# AlphaNumeric_Featherwing_rev_A.net
KiCad netlist of a schematic drawn in EAGLE
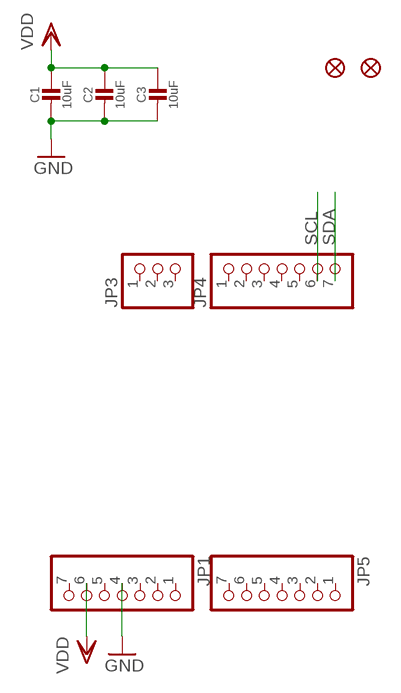
[diagram p0: schematic, sheet 1, part 1 of 2]
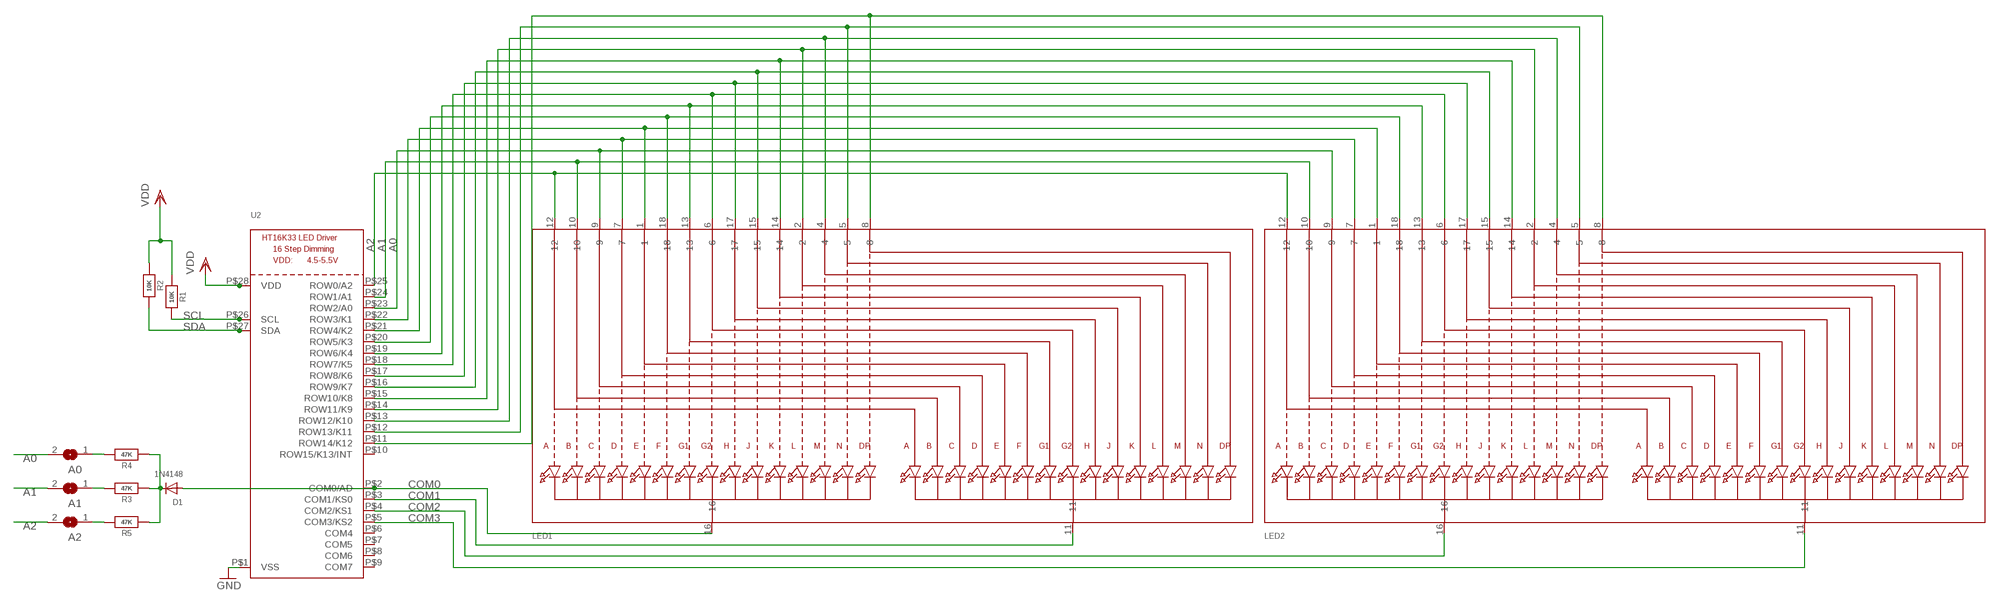
[diagram p1: schematic, sheet 1, part 2 of 2]

(export (version "E")
  (design (tool "Eeschema 10.0.6"))
  (components
    (comp (ref "A0")
      (value "SOLDERJUMPERREFLOW_NOPASTE")
      (footprint "eagle-import:SOLDERJUMPER_REFLOW_NOPASTE")
      (libsource (lib "eagle-import") (part "SOLDERJUMPERREFLOW_NOPASTE"))
    )
    (comp (ref "A1")
      (value "SOLDERJUMPERREFLOW_NOPASTE")
      (footprint "eagle-import:SOLDERJUMPER_REFLOW_NOPASTE")
      (libsource (lib "eagle-import") (part "SOLDERJUMPERREFLOW_NOPASTE"))
    )
    (comp (ref "A2")
      (value "SOLDERJUMPERREFLOW_NOPASTE")
      (footprint "eagle-import:SOLDERJUMPER_REFLOW_NOPASTE")
      (libsource (lib "eagle-import") (part "SOLDERJUMPERREFLOW_NOPASTE"))
    )
    (comp (ref "C1")
      (value "10uF")
      (footprint "eagle-import:0805-NO")
      (libsource (lib "eagle-import") (part "CAP_CERAMIC0805-NOOUTLINE"))
    )
    (comp (ref "C2")
      (value "10uF")
      (footprint "eagle-import:0805-NO")
      (libsource (lib "eagle-import") (part "CAP_CERAMIC0805-NOOUTLINE"))
    )
    (comp (ref "C3")
      (value "10uF")
      (footprint "eagle-import:0805-NO")
      (libsource (lib "eagle-import") (part "CAP_CERAMIC0805-NOOUTLINE"))
    )
    (comp (ref "D1")
      (value "1N4148")
      (footprint "eagle-import:SOD-323F")
      (libsource (lib "eagle-import") (part "DIODESOD-323F"))
    )
    (comp (ref "JP1")
      (value "HEADER-1X770MIL")
      (footprint "eagle-import:1X07_ROUND_70")
      (libsource (lib "eagle-import") (part "HEADER-1X770MIL"))
    )
    (comp (ref "JP3")
      (value "HEADER-1X3ROUND")
      (footprint "eagle-import:1X03_ROUND")
      (libsource (lib "eagle-import") (part "HEADER-1X3ROUND"))
    )
    (comp (ref "JP4")
      (value "HEADER-1X770MIL")
      (footprint "eagle-import:1X07_ROUND_70")
      (libsource (lib "eagle-import") (part "HEADER-1X770MIL"))
    )
    (comp (ref "JP5")
      (value "HEADER-1X770MIL")
      (footprint "eagle-import:1X07_ROUND_70")
      (libsource (lib "eagle-import") (part "HEADER-1X770MIL"))
    )
    (comp (ref "LED1")
      (value "DISP_SEGMENT_STARBURST_DUAL_COMMONCATHODE")
      (footprint "eagle-import:SEGMENT_STARTBUST_DUAL_KWA-541CBB")
      (libsource (lib "eagle-import") (part "DISP_SEGMENT_STARBURST_DUAL_COMMONCATHODE"))
    )
    (comp (ref "LED2")
      (value "DISP_SEGMENT_STARBURST_DUAL_COMMONCATHODE")
      (footprint "eagle-import:SEGMENT_STARTBUST_DUAL_KWA-541CBB")
      (libsource (lib "eagle-import") (part "DISP_SEGMENT_STARBURST_DUAL_COMMONCATHODE"))
    )
    (comp (ref "R1")
      (value "10K")
      (footprint "eagle-import:0805-NO")
      (libsource (lib "eagle-import") (part "RESISTOR0805_NOOUTLINE"))
    )
    (comp (ref "R2")
      (value "10K")
      (footprint "eagle-import:0805-NO")
      (libsource (lib "eagle-import") (part "RESISTOR0805_NOOUTLINE"))
    )
    (comp (ref "R3")
      (value "47K")
      (footprint "eagle-import:0805-NO")
      (libsource (lib "eagle-import") (part "RESISTOR0805_NOOUTLINE"))
    )
    (comp (ref "R4")
      (value "47K")
      (footprint "eagle-import:0805-NO")
      (libsource (lib "eagle-import") (part "RESISTOR0805_NOOUTLINE"))
    )
    (comp (ref "R5")
      (value "47K")
      (footprint "eagle-import:0805-NO")
      (libsource (lib "eagle-import") (part "RESISTOR0805_NOOUTLINE"))
    )
    (comp (ref "U$1")
      (value "FIDUCIAL\"\"")
      (footprint "eagle-import:FIDUCIAL_1MM")
      (libsource (lib "eagle-import") (part "FIDUCIAL{dblquote}{dblquote}"))
    )
    (comp (ref "U$2")
      (value "FIDUCIAL\"\"")
      (footprint "eagle-import:FIDUCIAL_1MM")
      (libsource (lib "eagle-import") (part "FIDUCIAL{dblquote}{dblquote}"))
    )
    (comp (ref "U2")
      (value "HT16K33_SOP28_SKINNY")
      (footprint "eagle-import:SOP28_300MIL_SKINNY")
      (libsource (lib "eagle-import") (part "HT16K33_SOP28_SKINNY"))
    )
  )
  (nets
    (net (code "1") (name "/A0") (class "Default")
      (node (ref "A0") (pin "2") (pinfunction "2_2") (pintype "passive"))
      (node (ref "LED1") (pin "9") (pinfunction "9_9") (pintype "bidirectional"))
      (node (ref "LED2") (pin "9") (pinfunction "9_9") (pintype "bidirectional"))
      (node (ref "U2") (pin "P$23") (pinfunction "ROW2/A0_P$23") (pintype "bidirectional"))
    )
    (net (code "2") (name "/A1") (class "Default")
      (node (ref "A1") (pin "2") (pinfunction "2_2") (pintype "passive"))
      (node (ref "LED1") (pin "10") (pinfunction "10_10") (pintype "bidirectional"))
      (node (ref "LED2") (pin "10") (pinfunction "10_10") (pintype "bidirectional"))
      (node (ref "U2") (pin "P$24") (pinfunction "ROW1/A1_P$24") (pintype "bidirectional"))
    )
    (net (code "3") (name "/A2") (class "Default")
      (node (ref "A2") (pin "2") (pinfunction "2_2") (pintype "passive"))
      (node (ref "LED1") (pin "12") (pinfunction "12_12") (pintype "bidirectional"))
      (node (ref "LED2") (pin "12") (pinfunction "12_12") (pintype "bidirectional"))
      (node (ref "U2") (pin "P$25") (pinfunction "ROW0/A2_P$25") (pintype "bidirectional"))
    )
    (net (code "4") (name "/COM0") (class "Default")
      (node (ref "D1") (pin "A") (pinfunction "A_A") (pintype "passive"))
      (node (ref "LED1") (pin "16") (pinfunction "16_16") (pintype "bidirectional"))
      (node (ref "U2") (pin "P$2") (pinfunction "COM0/AD_P$2") (pintype "bidirectional"))
    )
    (net (code "5") (name "/COM1") (class "Default")
      (node (ref "LED1") (pin "11") (pinfunction "11_11") (pintype "bidirectional"))
      (node (ref "U2") (pin "P$3") (pinfunction "COM1/KS0_P$3") (pintype "bidirectional"))
    )
    (net (code "6") (name "/COM2") (class "Default")
      (node (ref "LED2") (pin "16") (pinfunction "16_16") (pintype "bidirectional"))
      (node (ref "U2") (pin "P$4") (pinfunction "COM2/KS1_P$4") (pintype "bidirectional"))
    )
    (net (code "7") (name "/COM3") (class "Default")
      (node (ref "LED2") (pin "11") (pinfunction "11_11") (pintype "bidirectional"))
      (node (ref "U2") (pin "P$5") (pinfunction "COM3/KS2_P$5") (pintype "bidirectional"))
    )
    (net (code "8") (name "/SCL") (class "Default")
      (node (ref "JP4") (pin "6") (pinfunction "6_6") (pintype "passive"))
      (node (ref "R1") (pin "2") (pinfunction "2_2") (pintype "passive"))
      (node (ref "U2") (pin "P$26") (pinfunction "SCL_P$26") (pintype "bidirectional"))
    )
    (net (code "9") (name "/SDA") (class "Default")
      (node (ref "JP4") (pin "7") (pinfunction "7_7") (pintype "passive"))
      (node (ref "R2") (pin "2") (pinfunction "2_2") (pintype "passive"))
      (node (ref "U2") (pin "P$27") (pinfunction "SDA_P$27") (pintype "bidirectional"))
    )
    (net (code "10") (name "GND") (class "Default")
      (node (ref "C1") (pin "2") (pinfunction "2_2") (pintype "passive"))
      (node (ref "C2") (pin "2") (pinfunction "2_2") (pintype "passive"))
      (node (ref "C3") (pin "2") (pinfunction "2_2") (pintype "passive"))
      (node (ref "JP1") (pin "4") (pinfunction "4_4") (pintype "passive"))
      (node (ref "U2") (pin "P$1") (pinfunction "VSS_P$1") (pintype "bidirectional"))
    )
    (net (code "11") (name "Net-(A0-Pad1)") (class "Default")
      (node (ref "A0") (pin "1") (pinfunction "1_1") (pintype "passive"))
      (node (ref "R4") (pin "2") (pinfunction "2_2") (pintype "passive"))
    )
    (net (code "12") (name "Net-(A1-Pad1)") (class "Default")
      (node (ref "A1") (pin "1") (pinfunction "1_1") (pintype "passive"))
      (node (ref "R3") (pin "2") (pinfunction "2_2") (pintype "passive"))
    )
    (net (code "13") (name "Net-(A2-Pad1)") (class "Default")
      (node (ref "A2") (pin "1") (pinfunction "1_1") (pintype "passive"))
      (node (ref "R5") (pin "2") (pinfunction "2_2") (pintype "passive"))
    )
    (net (code "14") (name "Net-(D1-PadC)") (class "Default")
      (node (ref "D1") (pin "C") (pinfunction "C_C") (pintype "passive"))
      (node (ref "R3") (pin "1") (pinfunction "1_1") (pintype "passive"))
      (node (ref "R4") (pin "1") (pinfunction "1_1") (pintype "passive"))
      (node (ref "R5") (pin "1") (pinfunction "1_1") (pintype "passive"))
    )
    (net (code "15") (name "Net-(U2-ROW3{slash}K1)") (class "Default")
      (node (ref "LED1") (pin "7") (pinfunction "7_7") (pintype "bidirectional"))
      (node (ref "LED2") (pin "7") (pinfunction "7_7") (pintype "bidirectional"))
      (node (ref "U2") (pin "P$22") (pinfunction "ROW3/K1_P$22") (pintype "bidirectional"))
    )
    (net (code "16") (name "Net-(U2-ROW4{slash}K2)") (class "Default")
      (node (ref "LED1") (pin "1") (pinfunction "1_1") (pintype "bidirectional"))
      (node (ref "LED2") (pin "1") (pinfunction "1_1") (pintype "bidirectional"))
      (node (ref "U2") (pin "P$21") (pinfunction "ROW4/K2_P$21") (pintype "bidirectional"))
    )
    (net (code "17") (name "Net-(U2-ROW5{slash}K3)") (class "Default")
      (node (ref "LED1") (pin "18") (pinfunction "18_18") (pintype "bidirectional"))
      (node (ref "LED2") (pin "18") (pinfunction "18_18") (pintype "bidirectional"))
      (node (ref "U2") (pin "P$20") (pinfunction "ROW5/K3_P$20") (pintype "bidirectional"))
    )
    (net (code "18") (name "Net-(U2-ROW6{slash}K4)") (class "Default")
      (node (ref "LED1") (pin "13") (pinfunction "13_13") (pintype "bidirectional"))
      (node (ref "LED2") (pin "13") (pinfunction "13_13") (pintype "bidirectional"))
      (node (ref "U2") (pin "P$19") (pinfunction "ROW6/K4_P$19") (pintype "bidirectional"))
    )
    (net (code "19") (name "Net-(U2-ROW7{slash}K5)") (class "Default")
      (node (ref "LED1") (pin "6") (pinfunction "6_6") (pintype "bidirectional"))
      (node (ref "LED2") (pin "6") (pinfunction "6_6") (pintype "bidirectional"))
      (node (ref "U2") (pin "P$18") (pinfunction "ROW7/K5_P$18") (pintype "bidirectional"))
    )
    (net (code "20") (name "Net-(U2-ROW8{slash}K6)") (class "Default")
      (node (ref "LED1") (pin "17") (pinfunction "17_17") (pintype "bidirectional"))
      (node (ref "LED2") (pin "17") (pinfunction "17_17") (pintype "bidirectional"))
      (node (ref "U2") (pin "P$17") (pinfunction "ROW8/K6_P$17") (pintype "bidirectional"))
    )
    (net (code "21") (name "Net-(U2-ROW9{slash}K7)") (class "Default")
      (node (ref "LED1") (pin "15") (pinfunction "15_15") (pintype "bidirectional"))
      (node (ref "LED2") (pin "15") (pinfunction "15_15") (pintype "bidirectional"))
      (node (ref "U2") (pin "P$16") (pinfunction "ROW9/K7_P$16") (pintype "bidirectional"))
    )
    (net (code "22") (name "Net-(U2-ROW10{slash}K8)") (class "Default")
      (node (ref "LED1") (pin "14") (pinfunction "14_14") (pintype "bidirectional"))
      (node (ref "LED2") (pin "14") (pinfunction "14_14") (pintype "bidirectional"))
      (node (ref "U2") (pin "P$15") (pinfunction "ROW10/K8_P$15") (pintype "bidirectional"))
    )
    (net (code "23") (name "Net-(U2-ROW11{slash}K9)") (class "Default")
      (node (ref "LED1") (pin "2") (pinfunction "2_2") (pintype "bidirectional"))
      (node (ref "LED2") (pin "2") (pinfunction "2_2") (pintype "bidirectional"))
      (node (ref "U2") (pin "P$14") (pinfunction "ROW11/K9_P$14") (pintype "bidirectional"))
    )
    (net (code "24") (name "Net-(U2-ROW12{slash}K10)") (class "Default")
      (node (ref "LED1") (pin "4") (pinfunction "4_4") (pintype "bidirectional"))
      (node (ref "LED2") (pin "4") (pinfunction "4_4") (pintype "bidirectional"))
      (node (ref "U2") (pin "P$13") (pinfunction "ROW12/K10_P$13") (pintype "bidirectional"))
    )
    (net (code "25") (name "Net-(U2-ROW13{slash}K11)") (class "Default")
      (node (ref "LED1") (pin "5") (pinfunction "5_5") (pintype "bidirectional"))
      (node (ref "LED2") (pin "5") (pinfunction "5_5") (pintype "bidirectional"))
      (node (ref "U2") (pin "P$12") (pinfunction "ROW13/K11_P$12") (pintype "bidirectional"))
    )
    (net (code "26") (name "Net-(U2-ROW14{slash}K12)") (class "Default")
      (node (ref "LED1") (pin "8") (pinfunction "8_8") (pintype "bidirectional"))
      (node (ref "LED2") (pin "8") (pinfunction "8_8") (pintype "bidirectional"))
      (node (ref "U2") (pin "P$11") (pinfunction "ROW14/K12_P$11") (pintype "bidirectional"))
    )
    (net (code "27") (name "VDD") (class "Default")
      (node (ref "C1") (pin "1") (pinfunction "1_1") (pintype "passive"))
      (node (ref "C2") (pin "1") (pinfunction "1_1") (pintype "passive"))
      (node (ref "C3") (pin "1") (pinfunction "1_1") (pintype "passive"))
      (node (ref "JP1") (pin "6") (pinfunction "6_6") (pintype "passive"))
      (node (ref "R1") (pin "1") (pinfunction "1_1") (pintype "passive"))
      (node (ref "R2") (pin "1") (pinfunction "1_1") (pintype "passive"))
      (node (ref "U2") (pin "P$28") (pinfunction "VDD_P$28") (pintype "bidirectional"))
    )
    (net (code "28") (name "unconnected-(JP1-Pad1)") (class "Default")
      (node (ref "JP1") (pin "1") (pinfunction "1_1") (pintype "passive"))
    )
    (net (code "29") (name "unconnected-(JP1-Pad2)") (class "Default")
      (node (ref "JP1") (pin "2") (pinfunction "2_2") (pintype "passive"))
    )
    (net (code "30") (name "unconnected-(JP1-Pad3)") (class "Default")
      (node (ref "JP1") (pin "3") (pinfunction "3_3") (pintype "passive"))
    )
    (net (code "31") (name "unconnected-(JP1-Pad5)") (class "Default")
      (node (ref "JP1") (pin "5") (pinfunction "5_5") (pintype "passive"))
    )
    (net (code "32") (name "unconnected-(JP1-Pad7)") (class "Default")
      (node (ref "JP1") (pin "7") (pinfunction "7_7") (pintype "passive"))
    )
    (net (code "33") (name "unconnected-(JP3-Pad1)") (class "Default")
      (node (ref "JP3") (pin "1") (pinfunction "1_1") (pintype "passive"))
    )
    (net (code "34") (name "unconnected-(JP3-Pad2)") (class "Default")
      (node (ref "JP3") (pin "2") (pinfunction "2_2") (pintype "passive"))
    )
    (net (code "35") (name "unconnected-(JP3-Pad3)") (class "Default")
      (node (ref "JP3") (pin "3") (pinfunction "3_3") (pintype "passive"))
    )
    (net (code "36") (name "unconnected-(JP4-Pad1)") (class "Default")
      (node (ref "JP4") (pin "1") (pinfunction "1_1") (pintype "passive"))
    )
    (net (code "37") (name "unconnected-(JP4-Pad2)") (class "Default")
      (node (ref "JP4") (pin "2") (pinfunction "2_2") (pintype "passive"))
    )
    (net (code "38") (name "unconnected-(JP4-Pad3)") (class "Default")
      (node (ref "JP4") (pin "3") (pinfunction "3_3") (pintype "passive"))
    )
    (net (code "39") (name "unconnected-(JP4-Pad4)") (class "Default")
      (node (ref "JP4") (pin "4") (pinfunction "4_4") (pintype "passive"))
    )
    (net (code "40") (name "unconnected-(JP4-Pad5)") (class "Default")
      (node (ref "JP4") (pin "5") (pinfunction "5_5") (pintype "passive"))
    )
    (net (code "41") (name "unconnected-(JP5-Pad1)") (class "Default")
      (node (ref "JP5") (pin "1") (pinfunction "1_1") (pintype "passive"))
    )
    (net (code "42") (name "unconnected-(JP5-Pad2)") (class "Default")
      (node (ref "JP5") (pin "2") (pinfunction "2_2") (pintype "passive"))
    )
    (net (code "43") (name "unconnected-(JP5-Pad3)") (class "Default")
      (node (ref "JP5") (pin "3") (pinfunction "3_3") (pintype "passive"))
    )
    (net (code "44") (name "unconnected-(JP5-Pad4)") (class "Default")
      (node (ref "JP5") (pin "4") (pinfunction "4_4") (pintype "passive"))
    )
    (net (code "45") (name "unconnected-(JP5-Pad5)") (class "Default")
      (node (ref "JP5") (pin "5") (pinfunction "5_5") (pintype "passive"))
    )
    (net (code "46") (name "unconnected-(JP5-Pad6)") (class "Default")
      (node (ref "JP5") (pin "6") (pinfunction "6_6") (pintype "passive"))
    )
    (net (code "47") (name "unconnected-(JP5-Pad7)") (class "Default")
      (node (ref "JP5") (pin "7") (pinfunction "7_7") (pintype "passive"))
    )
    (net (code "48") (name "unconnected-(U2-COM4-PadP$6)") (class "Default")
      (node (ref "U2") (pin "P$6") (pinfunction "COM4_P$6") (pintype "bidirectional"))
    )
    (net (code "49") (name "unconnected-(U2-COM5-PadP$7)") (class "Default")
      (node (ref "U2") (pin "P$7") (pinfunction "COM5_P$7") (pintype "bidirectional"))
    )
    (net (code "50") (name "unconnected-(U2-COM6-PadP$8)") (class "Default")
      (node (ref "U2") (pin "P$8") (pinfunction "COM6_P$8") (pintype "bidirectional"))
    )
    (net (code "51") (name "unconnected-(U2-COM7-PadP$9)") (class "Default")
      (node (ref "U2") (pin "P$9") (pinfunction "COM7_P$9") (pintype "bidirectional"))
    )
    (net (code "52") (name "unconnected-(U2-ROW15{slash}K13{slash}INT-PadP$10)") (class "Default")
      (node (ref "U2") (pin "P$10") (pinfunction "ROW15/K13/INT_P$10") (pintype "bidirectional"))
    )
  )
)
